# ATMegaTestingBoard.net
KiCad netlist of a schematic drawn in EAGLE
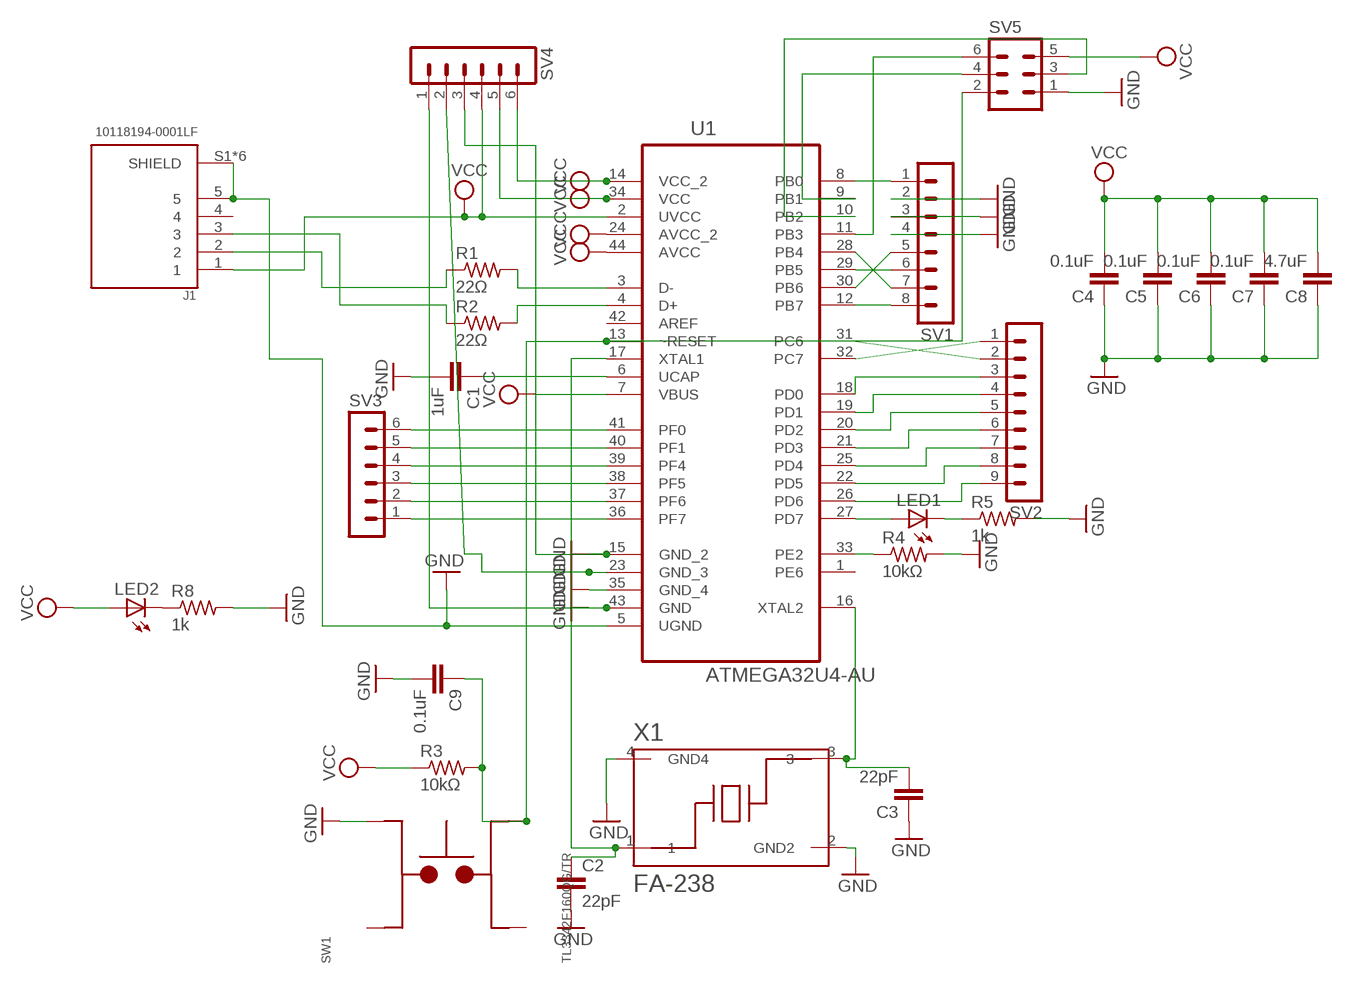
[diagram p0: schematic, sheet 1]

(export (version "E")
  (design (tool "Eeschema 10.0.6"))
  (components
    (comp (ref "C1")
      (value "1uF")
      (footprint "eagle-import:C0805")
      (libsource (lib "eagle-import") (part "C-EUC0805"))
    )
    (comp (ref "C2")
      (value "22pF")
      (footprint "eagle-import:C0805")
      (libsource (lib "eagle-import") (part "C-EUC0805"))
    )
    (comp (ref "C3")
      (value "22pF")
      (footprint "eagle-import:C0805")
      (libsource (lib "eagle-import") (part "C-EUC0805"))
    )
    (comp (ref "C4")
      (value "0.1uF")
      (footprint "eagle-import:C0805")
      (libsource (lib "eagle-import") (part "C-EUC0805"))
    )
    (comp (ref "C5")
      (value "0.1uF")
      (footprint "eagle-import:C0805")
      (libsource (lib "eagle-import") (part "C-EUC0805"))
    )
    (comp (ref "C6")
      (value "0.1uF")
      (footprint "eagle-import:C0805")
      (libsource (lib "eagle-import") (part "C-EUC0805"))
    )
    (comp (ref "C7")
      (value "0.1uF")
      (footprint "eagle-import:C0805")
      (libsource (lib "eagle-import") (part "C-EUC0805"))
    )
    (comp (ref "C8")
      (value "4.7uF")
      (footprint "eagle-import:C0805")
      (libsource (lib "eagle-import") (part "C-EUC0805"))
    )
    (comp (ref "C9")
      (value "0.1uF")
      (footprint "eagle-import:C0805")
      (libsource (lib "eagle-import") (part "C-EUC0805"))
    )
    (comp (ref "J1")
      (value "10118194-0001LF")
      (footprint "eagle-import:AMPHENOL_10118194-0001LF")
      (fields (field (name "MF") "Amphenol ICC"))
      (libsource (lib "eagle-import") (part "10118194-0001LF"))
    )
    (comp (ref "LED1")
      (value "LEDCHIPLED_0805")
      (footprint "eagle-import:CHIPLED_0805")
      (libsource (lib "eagle-import") (part "LEDCHIPLED_0805"))
    )
    (comp (ref "LED2")
      (value "LEDCHIPLED_0805")
      (footprint "eagle-import:CHIPLED_0805")
      (libsource (lib "eagle-import") (part "LEDCHIPLED_0805"))
    )
    (comp (ref "R1")
      (value "22Ω")
      (footprint "eagle-import:R0805")
      (libsource (lib "eagle-import") (part "R-US_R0805"))
    )
    (comp (ref "R2")
      (value "22Ω")
      (footprint "eagle-import:R0805")
      (libsource (lib "eagle-import") (part "R-US_R0805"))
    )
    (comp (ref "R3")
      (value "10kΩ")
      (footprint "eagle-import:R0805")
      (libsource (lib "eagle-import") (part "R-US_R0805"))
    )
    (comp (ref "R4")
      (value "10kΩ")
      (footprint "eagle-import:R0805")
      (libsource (lib "eagle-import") (part "R-US_R0805"))
    )
    (comp (ref "R5")
      (value "1k")
      (footprint "eagle-import:R0805")
      (libsource (lib "eagle-import") (part "R-US_R0805"))
    )
    (comp (ref "R8")
      (value "1k")
      (footprint "eagle-import:R0805")
      (libsource (lib "eagle-import") (part "R-US_R0805"))
    )
    (comp (ref "SV1")
      (value "MA08-1")
      (footprint "eagle-import:MA08-1")
      (libsource (lib "eagle-import") (part "MA08-1"))
    )
    (comp (ref "SV2")
      (value "MA09-1")
      (footprint "eagle-import:MA09-1")
      (libsource (lib "eagle-import") (part "MA09-1"))
    )
    (comp (ref "SV3")
      (value "MA06-1")
      (footprint "eagle-import:MA06-1")
      (libsource (lib "eagle-import") (part "MA06-1"))
    )
    (comp (ref "SV4")
      (value "MA06-1")
      (footprint "eagle-import:MA06-1")
      (libsource (lib "eagle-import") (part "MA06-1"))
    )
    (comp (ref "SV5")
      (value "MA03-2")
      (footprint "eagle-import:MA03-2")
      (libsource (lib "eagle-import") (part "MA03-2"))
    )
    (comp (ref "SW1")
      (value "TL3342F160QG/TR")
      (footprint "eagle-import:SW_TL3342F160QG_TR")
      (fields (field (name "DIGI-KEY_PART_NUMBER") "EG2531CT-ND") (field (name "MF") "E-Switch"))
      (libsource (lib "eagle-import") (part "TL3342F160QG/TR"))
    )
    (comp (ref "U1")
      (value "ATMEGA32U4-AU")
      (footprint "eagle-import:QFP80P1200X1200X120-44N")
      (fields (field (name "MF") "Microchip"))
      (libsource (lib "eagle-import") (part "ATMEGA32U4-AU"))
    )
    (comp (ref "X1")
      (value "FA-238")
      (footprint "eagle-import:OSCCC320X250X70-4N")
      (fields (field (name "MF") "EPSON"))
      (libsource (lib "eagle-import") (part "FA-238"))
    )
  )
  (nets
    (net (code "1") (name "GND") (class "Default")
      (node (ref "C1") (pin "2") (pinfunction "2_2") (pintype "passive"))
      (node (ref "C2") (pin "2") (pinfunction "2_2") (pintype "passive"))
      (node (ref "C3") (pin "1") (pinfunction "1_1") (pintype "passive"))
      (node (ref "C4") (pin "1") (pinfunction "1_1") (pintype "passive"))
      (node (ref "C5") (pin "1") (pinfunction "1_1") (pintype "passive"))
      (node (ref "C6") (pin "1") (pinfunction "1_1") (pintype "passive"))
      (node (ref "C7") (pin "1") (pinfunction "1_1") (pintype "passive"))
      (node (ref "C8") (pin "1") (pinfunction "1_1") (pintype "passive"))
      (node (ref "C9") (pin "2") (pinfunction "2_2") (pintype "passive"))
      (node (ref "J1") (pin "5") (pinfunction "5_5") (pintype "passive"))
      (node (ref "J1") (pin "S1") (pinfunction "SHIELD_S1") (pintype "passive"))
      (node (ref "J1") (pin "S2") (pinfunction "SHIELD_S2") (pintype "passive"))
      (node (ref "J1") (pin "S3") (pinfunction "SHIELD_S3") (pintype "passive"))
      (node (ref "J1") (pin "S4") (pinfunction "SHIELD_S4") (pintype "passive"))
      (node (ref "J1") (pin "S5") (pinfunction "SHIELD_S5") (pintype "passive"))
      (node (ref "J1") (pin "S6") (pinfunction "SHIELD_S6") (pintype "passive"))
      (node (ref "R4") (pin "2") (pinfunction "2_2") (pintype "passive"))
      (node (ref "R5") (pin "2") (pinfunction "2_2") (pintype "passive"))
      (node (ref "R8") (pin "2") (pinfunction "2_2") (pintype "passive"))
      (node (ref "SV1") (pin "2") (pinfunction "2_2") (pintype "passive"))
      (node (ref "SV1") (pin "3") (pinfunction "3_3") (pintype "passive"))
      (node (ref "SV1") (pin "4") (pinfunction "4_4") (pintype "passive"))
      (node (ref "SV4") (pin "1") (pinfunction "1_1") (pintype "passive"))
      (node (ref "SV4") (pin "2") (pinfunction "2_2") (pintype "passive"))
      (node (ref "SV4") (pin "3") (pinfunction "3_3") (pintype "passive"))
      (node (ref "SV5") (pin "1") (pinfunction "1_1") (pintype "passive"))
      (node (ref "SW1") (pin "4") (pinfunction "4_4") (pintype "passive"))
      (node (ref "U1") (pin "15") (pinfunction "GND_2_15") (pintype "passive"))
      (node (ref "U1") (pin "23") (pinfunction "GND_3_23") (pintype "passive"))
      (node (ref "U1") (pin "35") (pinfunction "GND_4_35") (pintype "passive"))
      (node (ref "U1") (pin "43") (pinfunction "GND_43") (pintype "passive"))
      (node (ref "U1") (pin "5") (pinfunction "UGND_5") (pintype "passive"))
      (node (ref "X1") (pin "2") (pinfunction "GND2_2") (pintype "passive"))
      (node (ref "X1") (pin "4") (pinfunction "GND4_4") (pintype "passive"))
    )
    (net (code "2") (name "Net-(J1-Pad2)") (class "Default")
      (node (ref "J1") (pin "2") (pinfunction "2_2") (pintype "passive"))
      (node (ref "R1") (pin "1") (pinfunction "1_1") (pintype "passive"))
    )
    (net (code "3") (name "Net-(J1-Pad3)") (class "Default")
      (node (ref "J1") (pin "3") (pinfunction "3_3") (pintype "passive"))
      (node (ref "R2") (pin "1") (pinfunction "1_1") (pintype "passive"))
    )
    (net (code "4") (name "Net-(LED1-PadC)") (class "Default")
      (node (ref "LED1") (pin "C") (pinfunction "C_C") (pintype "passive"))
      (node (ref "R5") (pin "1") (pinfunction "1_1") (pintype "passive"))
    )
    (net (code "5") (name "Net-(LED2-PadC)") (class "Default")
      (node (ref "LED2") (pin "C") (pinfunction "C_C") (pintype "passive"))
      (node (ref "R8") (pin "1") (pinfunction "1_1") (pintype "passive"))
    )
    (net (code "6") (name "Net-(U1-D+)") (class "Default")
      (node (ref "R2") (pin "2") (pinfunction "2_2") (pintype "passive"))
      (node (ref "U1") (pin "4") (pinfunction "D+_4") (pintype "passive"))
    )
    (net (code "7") (name "Net-(U1-D-)") (class "Default")
      (node (ref "R1") (pin "2") (pinfunction "2_2") (pintype "passive"))
      (node (ref "U1") (pin "3") (pinfunction "D-_3") (pintype "passive"))
    )
    (net (code "8") (name "Net-(U1-PB0)") (class "Default")
      (node (ref "SV1") (pin "1") (pinfunction "1_1") (pintype "passive"))
      (node (ref "U1") (pin "8") (pinfunction "PB0_8") (pintype "bidirectional"))
    )
    (net (code "9") (name "Net-(U1-PB1)") (class "Default")
      (node (ref "SV5") (pin "4") (pinfunction "4_4") (pintype "passive"))
      (node (ref "U1") (pin "9") (pinfunction "PB1_9") (pintype "bidirectional"))
    )
    (net (code "10") (name "Net-(U1-PB2)") (class "Default")
      (node (ref "SV5") (pin "3") (pinfunction "3_3") (pintype "passive"))
      (node (ref "U1") (pin "10") (pinfunction "PB2_10") (pintype "bidirectional"))
    )
    (net (code "11") (name "Net-(U1-PB3)") (class "Default")
      (node (ref "SV5") (pin "6") (pinfunction "6_6") (pintype "passive"))
      (node (ref "U1") (pin "11") (pinfunction "PB3_11") (pintype "bidirectional"))
    )
    (net (code "12") (name "Net-(U1-PB4)") (class "Default")
      (node (ref "SV1") (pin "7") (pinfunction "7_7") (pintype "passive"))
      (node (ref "U1") (pin "28") (pinfunction "PB4_28") (pintype "bidirectional"))
    )
    (net (code "13") (name "Net-(U1-PB5)") (class "Default")
      (node (ref "SV1") (pin "6") (pinfunction "6_6") (pintype "passive"))
      (node (ref "U1") (pin "29") (pinfunction "PB5_29") (pintype "bidirectional"))
    )
    (net (code "14") (name "Net-(U1-PB6)") (class "Default")
      (node (ref "SV1") (pin "5") (pinfunction "5_5") (pintype "passive"))
      (node (ref "U1") (pin "30") (pinfunction "PB6_30") (pintype "bidirectional"))
    )
    (net (code "15") (name "Net-(U1-PB7)") (class "Default")
      (node (ref "SV1") (pin "8") (pinfunction "8_8") (pintype "passive"))
      (node (ref "U1") (pin "12") (pinfunction "PB7_12") (pintype "bidirectional"))
    )
    (net (code "16") (name "Net-(U1-PC6)") (class "Default")
      (node (ref "SV2") (pin "2") (pinfunction "2_2") (pintype "passive"))
      (node (ref "U1") (pin "31") (pinfunction "PC6_31") (pintype "bidirectional"))
    )
    (net (code "17") (name "Net-(U1-PC7)") (class "Default")
      (node (ref "SV2") (pin "1") (pinfunction "1_1") (pintype "passive"))
      (node (ref "U1") (pin "32") (pinfunction "PC7_32") (pintype "bidirectional"))
    )
    (net (code "18") (name "Net-(U1-PD0)") (class "Default")
      (node (ref "SV2") (pin "3") (pinfunction "3_3") (pintype "passive"))
      (node (ref "U1") (pin "18") (pinfunction "PD0_18") (pintype "bidirectional"))
    )
    (net (code "19") (name "Net-(U1-PD1)") (class "Default")
      (node (ref "SV2") (pin "4") (pinfunction "4_4") (pintype "passive"))
      (node (ref "U1") (pin "19") (pinfunction "PD1_19") (pintype "bidirectional"))
    )
    (net (code "20") (name "Net-(U1-PD2)") (class "Default")
      (node (ref "SV2") (pin "5") (pinfunction "5_5") (pintype "passive"))
      (node (ref "U1") (pin "20") (pinfunction "PD2_20") (pintype "bidirectional"))
    )
    (net (code "21") (name "Net-(U1-PD3)") (class "Default")
      (node (ref "SV2") (pin "6") (pinfunction "6_6") (pintype "passive"))
      (node (ref "U1") (pin "21") (pinfunction "PD3_21") (pintype "bidirectional"))
    )
    (net (code "22") (name "Net-(U1-PD4)") (class "Default")
      (node (ref "SV2") (pin "7") (pinfunction "7_7") (pintype "passive"))
      (node (ref "U1") (pin "25") (pinfunction "PD4_25") (pintype "bidirectional"))
    )
    (net (code "23") (name "Net-(U1-PD5)") (class "Default")
      (node (ref "SV2") (pin "8") (pinfunction "8_8") (pintype "passive"))
      (node (ref "U1") (pin "22") (pinfunction "PD5_22") (pintype "bidirectional"))
    )
    (net (code "24") (name "Net-(U1-PD6)") (class "Default")
      (node (ref "SV2") (pin "9") (pinfunction "9_9") (pintype "passive"))
      (node (ref "U1") (pin "26") (pinfunction "PD6_26") (pintype "bidirectional"))
    )
    (net (code "25") (name "Net-(U1-PD7)") (class "Default")
      (node (ref "LED1") (pin "A") (pinfunction "A_A") (pintype "passive"))
      (node (ref "U1") (pin "27") (pinfunction "PD7_27") (pintype "bidirectional"))
    )
    (net (code "26") (name "Net-(U1-PE2)") (class "Default")
      (node (ref "R4") (pin "1") (pinfunction "1_1") (pintype "passive"))
      (node (ref "U1") (pin "33") (pinfunction "PE2_33") (pintype "bidirectional"))
    )
    (net (code "27") (name "Net-(U1-PF0)") (class "Default")
      (node (ref "SV3") (pin "6") (pinfunction "6_6") (pintype "passive"))
      (node (ref "U1") (pin "41") (pinfunction "PF0_41") (pintype "bidirectional"))
    )
    (net (code "28") (name "Net-(U1-PF1)") (class "Default")
      (node (ref "SV3") (pin "5") (pinfunction "5_5") (pintype "passive"))
      (node (ref "U1") (pin "40") (pinfunction "PF1_40") (pintype "bidirectional"))
    )
    (net (code "29") (name "Net-(U1-PF4)") (class "Default")
      (node (ref "SV3") (pin "4") (pinfunction "4_4") (pintype "passive"))
      (node (ref "U1") (pin "39") (pinfunction "PF4_39") (pintype "bidirectional"))
    )
    (net (code "30") (name "Net-(U1-PF5)") (class "Default")
      (node (ref "SV3") (pin "3") (pinfunction "3_3") (pintype "passive"))
      (node (ref "U1") (pin "38") (pinfunction "PF5_38") (pintype "bidirectional"))
    )
    (net (code "31") (name "Net-(U1-PF6)") (class "Default")
      (node (ref "SV3") (pin "2") (pinfunction "2_2") (pintype "passive"))
      (node (ref "U1") (pin "37") (pinfunction "PF6_37") (pintype "bidirectional"))
    )
    (net (code "32") (name "Net-(U1-PF7)") (class "Default")
      (node (ref "SV3") (pin "1") (pinfunction "1_1") (pintype "passive"))
      (node (ref "U1") (pin "36") (pinfunction "PF7_36") (pintype "bidirectional"))
    )
    (net (code "33") (name "Net-(U1-UCAP)") (class "Default")
      (node (ref "C1") (pin "1") (pinfunction "1_1") (pintype "passive"))
      (node (ref "U1") (pin "6") (pinfunction "UCAP_6") (pintype "power_in"))
    )
    (net (code "34") (name "Net-(U1-XTAL1)") (class "Default")
      (node (ref "C2") (pin "1") (pinfunction "1_1") (pintype "passive"))
      (node (ref "U1") (pin "17") (pinfunction "XTAL1_17") (pintype "input"))
      (node (ref "X1") (pin "1") (pinfunction "1_1") (pintype "passive"))
    )
    (net (code "35") (name "Net-(U1-XTAL2)") (class "Default")
      (node (ref "C3") (pin "2") (pinfunction "2_2") (pintype "passive"))
      (node (ref "U1") (pin "16") (pinfunction "XTAL2_16") (pintype "output"))
      (node (ref "X1") (pin "3") (pinfunction "3_3") (pintype "passive"))
    )
    (net (code "36") (name "Net-(U1-~{RESET})") (class "Default")
      (node (ref "C9") (pin "1") (pinfunction "1_1") (pintype "passive"))
      (node (ref "R3") (pin "2") (pinfunction "2_2") (pintype "passive"))
      (node (ref "SV5") (pin "2") (pinfunction "2_2") (pintype "passive"))
      (node (ref "SW1") (pin "2") (pinfunction "2_2") (pintype "passive"))
      (node (ref "U1") (pin "13") (pinfunction "~{RESET}_13") (pintype "input"))
    )
    (net (code "37") (name "VCC") (class "Default")
      (node (ref "C4") (pin "2") (pinfunction "2_2") (pintype "passive"))
      (node (ref "C5") (pin "2") (pinfunction "2_2") (pintype "passive"))
      (node (ref "C6") (pin "2") (pinfunction "2_2") (pintype "passive"))
      (node (ref "C7") (pin "2") (pinfunction "2_2") (pintype "passive"))
      (node (ref "C8") (pin "2") (pinfunction "2_2") (pintype "passive"))
      (node (ref "J1") (pin "1") (pinfunction "1_1") (pintype "passive"))
      (node (ref "LED2") (pin "A") (pinfunction "A_A") (pintype "passive"))
      (node (ref "R3") (pin "1") (pinfunction "1_1") (pintype "passive"))
      (node (ref "SV4") (pin "4") (pinfunction "4_4") (pintype "passive"))
      (node (ref "SV4") (pin "5") (pinfunction "5_5") (pintype "passive"))
      (node (ref "SV4") (pin "6") (pinfunction "6_6") (pintype "passive"))
      (node (ref "SV5") (pin "5") (pinfunction "5_5") (pintype "passive"))
      (node (ref "U1") (pin "14") (pinfunction "VCC_2_14") (pintype "power_in"))
      (node (ref "U1") (pin "2") (pinfunction "UVCC_2") (pintype "power_in"))
      (node (ref "U1") (pin "24") (pinfunction "AVCC_2_24") (pintype "power_in"))
      (node (ref "U1") (pin "34") (pinfunction "VCC_34") (pintype "power_in"))
      (node (ref "U1") (pin "44") (pinfunction "AVCC_44") (pintype "power_in"))
      (node (ref "U1") (pin "7") (pinfunction "VBUS_7") (pintype "input"))
    )
    (net (code "38") (name "unconnected-(J1-Pad4)") (class "Default")
      (node (ref "J1") (pin "4") (pinfunction "4_4") (pintype "passive"))
    )
    (net (code "39") (name "unconnected-(SW1-Pad1)") (class "Default")
      (node (ref "SW1") (pin "1") (pinfunction "1_1") (pintype "passive"))
    )
    (net (code "40") (name "unconnected-(SW1-Pad3)") (class "Default")
      (node (ref "SW1") (pin "3") (pinfunction "3_3") (pintype "passive"))
    )
    (net (code "41") (name "unconnected-(U1-AREF-Pad42)") (class "Default")
      (node (ref "U1") (pin "42") (pinfunction "AREF_42") (pintype "input"))
    )
    (net (code "42") (name "unconnected-(U1-PE6-Pad1)") (class "Default")
      (node (ref "U1") (pin "1") (pinfunction "PE6_1") (pintype "bidirectional"))
    )
  )
)
